# motorBoard.net
KiCad netlist of a schematic drawn in EAGLE
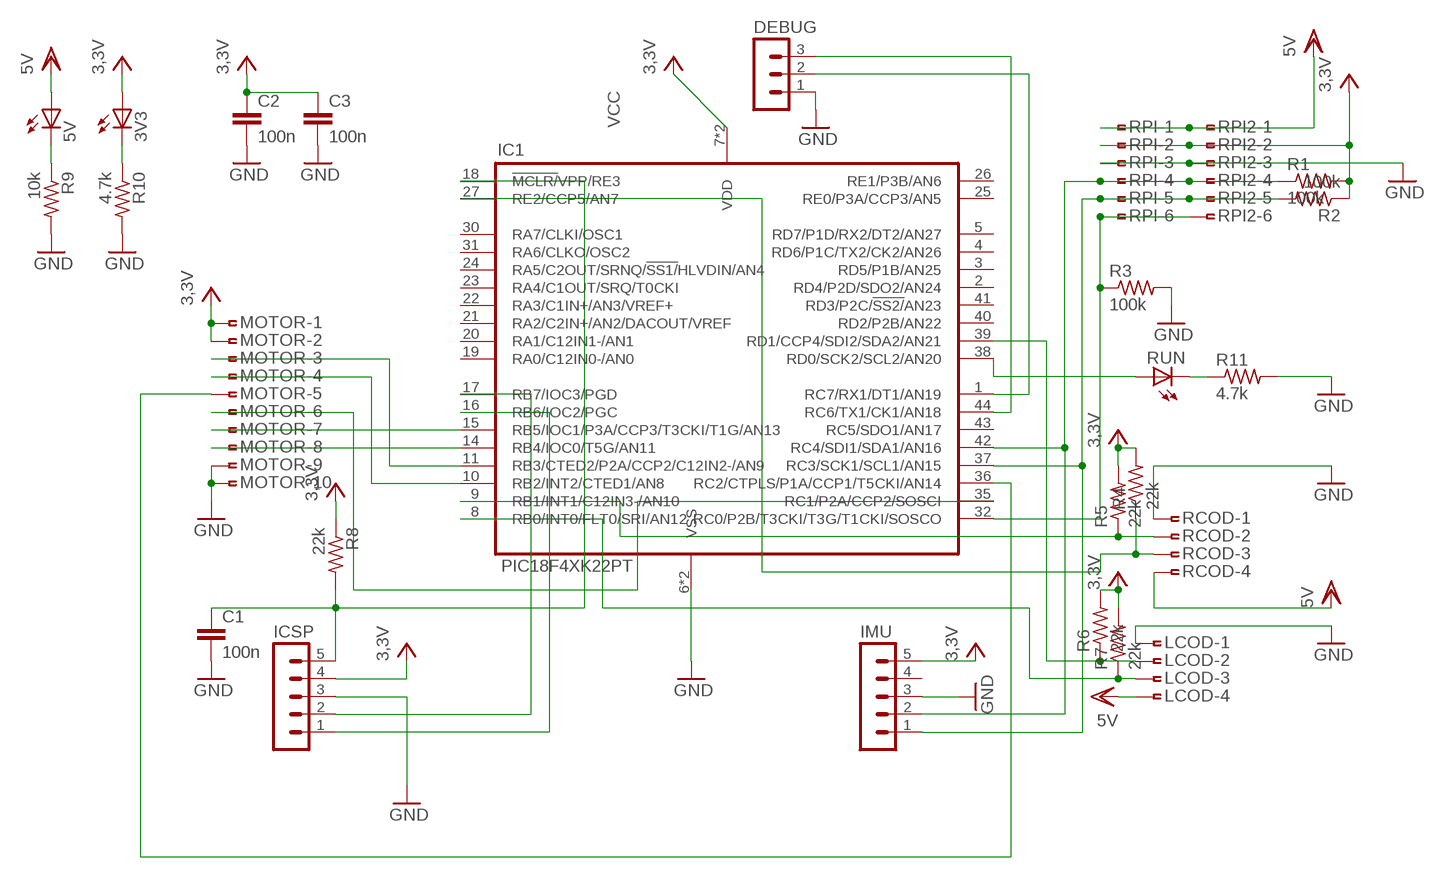
[diagram p0: schematic, sheet 1]

(export (version "E")
  (design (tool "Eeschema 10.0.6"))
  (components
    (comp (ref "3V3")
      (value "LEDCHIPLED_0805")
      (footprint "eagle-import:CHIPLED_0805")
      (libsource (lib "eagle-import") (part "LEDCHIPLED_0805"))
    )
    (comp (ref "5V")
      (value "LEDCHIPLED_0805")
      (footprint "eagle-import:CHIPLED_0805")
      (libsource (lib "eagle-import") (part "LEDCHIPLED_0805"))
    )
    (comp (ref "C1")
      (value "100n")
      (footprint "eagle-import:C0805")
      (libsource (lib "eagle-import") (part "C-EUC0805"))
    )
    (comp (ref "C2")
      (value "100n")
      (footprint "eagle-import:C0805")
      (libsource (lib "eagle-import") (part "C-EUC0805"))
    )
    (comp (ref "C3")
      (value "100n")
      (footprint "eagle-import:C0805")
      (libsource (lib "eagle-import") (part "C-EUC0805"))
    )
    (comp (ref "DEBUG")
      (value "MA03-1")
      (footprint "eagle-import:MA03-1")
      (libsource (lib "eagle-import") (part "MA03-1"))
    )
    (comp (ref "IC1")
      (value "PIC18F4XK22PT")
      (footprint "eagle-import:TQFP44")
      (libsource (lib "eagle-import") (part "PIC18F4XK22PT"))
    )
    (comp (ref "ICSP")
      (value "MA05-1")
      (footprint "eagle-import:MA05-1")
      (libsource (lib "eagle-import") (part "MA05-1"))
    )
    (comp (ref "IMU")
      (value "MA05-1")
      (footprint "eagle-import:MA05-1")
      (libsource (lib "eagle-import") (part "MA05-1"))
    )
    (comp (ref "LCOD")
      (value "SMDTOP-4")
      (footprint "eagle-import:SMDTOP4")
      (libsource (lib "eagle-import") (part "SMDTOP-4"))
    )
    (comp (ref "MOTOR")
      (value "SMDTOP-10")
      (footprint "eagle-import:SMDTOP10")
      (libsource (lib "eagle-import") (part "SMDTOP-10"))
    )
    (comp (ref "R1")
      (value "100k")
      (footprint "eagle-import:R0805")
      (libsource (lib "eagle-import") (part "R-US_R0805"))
    )
    (comp (ref "R2")
      (value "100k")
      (footprint "eagle-import:R0805")
      (libsource (lib "eagle-import") (part "R-US_R0805"))
    )
    (comp (ref "R3")
      (value "100k")
      (footprint "eagle-import:R0805")
      (libsource (lib "eagle-import") (part "R-US_R0805"))
    )
    (comp (ref "R4")
      (value "22k")
      (footprint "eagle-import:R0805")
      (libsource (lib "eagle-import") (part "R-US_R0805"))
    )
    (comp (ref "R5")
      (value "22k")
      (footprint "eagle-import:R0805")
      (libsource (lib "eagle-import") (part "R-US_R0805"))
    )
    (comp (ref "R6")
      (value "22k")
      (footprint "eagle-import:R0805")
      (libsource (lib "eagle-import") (part "R-US_R0805"))
    )
    (comp (ref "R7")
      (value "22k")
      (footprint "eagle-import:R0805")
      (libsource (lib "eagle-import") (part "R-US_R0805"))
    )
    (comp (ref "R8")
      (value "22k")
      (footprint "eagle-import:M0805")
      (libsource (lib "eagle-import") (part "R-US_M0805"))
    )
    (comp (ref "R9")
      (value "10k")
      (footprint "eagle-import:M0805")
      (libsource (lib "eagle-import") (part "R-US_M0805"))
    )
    (comp (ref "R10")
      (value "4.7k")
      (footprint "eagle-import:M0805")
      (libsource (lib "eagle-import") (part "R-US_M0805"))
    )
    (comp (ref "R11")
      (value "4.7k")
      (footprint "eagle-import:M0805")
      (libsource (lib "eagle-import") (part "R-US_M0805"))
    )
    (comp (ref "RCOD")
      (value "SMDTOP-4")
      (footprint "eagle-import:SMDTOP4")
      (libsource (lib "eagle-import") (part "SMDTOP-4"))
    )
    (comp (ref "RPI")
      (value "SMDTOP-6")
      (footprint "eagle-import:SMDTOP6")
      (libsource (lib "eagle-import") (part "SMDTOP-6"))
    )
    (comp (ref "RPI2")
      (value "SMDTOP-6")
      (footprint "eagle-import:SMDTOP6")
      (libsource (lib "eagle-import") (part "SMDTOP-6"))
    )
    (comp (ref "RUN")
      (value "LEDCHIPLED_0805")
      (footprint "eagle-import:CHIPLED_0805")
      (libsource (lib "eagle-import") (part "LEDCHIPLED_0805"))
    )
  )
  (nets
    (net (code "1") (name "3,3V") (class "Default")
      (node (ref "3V3") (pin "A") (pinfunction "A_A") (pintype "passive"))
      (node (ref "C2") (pin "1") (pinfunction "1_1") (pintype "passive"))
      (node (ref "C3") (pin "1") (pinfunction "1_1") (pintype "passive"))
      (node (ref "IC1") (pin "28") (pinfunction "VDD_28") (pintype "power_in"))
      (node (ref "IC1") (pin "7") (pinfunction "VDD_7") (pintype "power_in"))
      (node (ref "ICSP") (pin "4") (pinfunction "4_4") (pintype "passive"))
      (node (ref "IMU") (pin "5") (pinfunction "5_5") (pintype "passive"))
      (node (ref "MOTOR") (pin "1") (pinfunction "1_1") (pintype "passive"))
      (node (ref "MOTOR") (pin "2") (pinfunction "1_2") (pintype "passive"))
      (node (ref "R1") (pin "2") (pinfunction "2_2") (pintype "passive"))
      (node (ref "R2") (pin "1") (pinfunction "1_1") (pintype "passive"))
      (node (ref "R4") (pin "2") (pinfunction "2_2") (pintype "passive"))
      (node (ref "R5") (pin "2") (pinfunction "2_2") (pintype "passive"))
      (node (ref "R6") (pin "2") (pinfunction "2_2") (pintype "passive"))
      (node (ref "R7") (pin "2") (pinfunction "2_2") (pintype "passive"))
      (node (ref "R8") (pin "1") (pinfunction "1_1") (pintype "passive"))
      (node (ref "RPI") (pin "2") (pinfunction "1_2") (pintype "passive"))
      (node (ref "RPI2") (pin "2") (pinfunction "1_2") (pintype "passive"))
    )
    (net (code "2") (name "5V") (class "Default")
      (node (ref "5V") (pin "A") (pinfunction "A_A") (pintype "passive"))
      (node (ref "LCOD") (pin "4") (pinfunction "1_4") (pintype "passive"))
      (node (ref "RCOD") (pin "4") (pinfunction "1_4") (pintype "passive"))
      (node (ref "RPI") (pin "1") (pinfunction "1_1") (pintype "passive"))
      (node (ref "RPI2") (pin "1") (pinfunction "1_1") (pintype "passive"))
    )
    (net (code "3") (name "GND") (class "Default")
      (node (ref "C1") (pin "2") (pinfunction "2_2") (pintype "passive"))
      (node (ref "C2") (pin "2") (pinfunction "2_2") (pintype "passive"))
      (node (ref "C3") (pin "2") (pinfunction "2_2") (pintype "passive"))
      (node (ref "DEBUG") (pin "1") (pinfunction "1_1") (pintype "passive"))
      (node (ref "IC1") (pin "29") (pinfunction "VSS_29") (pintype "power_in"))
      (node (ref "IC1") (pin "6") (pinfunction "VSS_6") (pintype "power_in"))
      (node (ref "ICSP") (pin "3") (pinfunction "3_3") (pintype "passive"))
      (node (ref "IMU") (pin "3") (pinfunction "3_3") (pintype "passive"))
      (node (ref "LCOD") (pin "1") (pinfunction "1_1") (pintype "passive"))
      (node (ref "MOTOR") (pin "10") (pinfunction "1_10") (pintype "passive"))
      (node (ref "MOTOR") (pin "9") (pinfunction "1_9") (pintype "passive"))
      (node (ref "R10") (pin "2") (pinfunction "2_2") (pintype "passive"))
      (node (ref "R11") (pin "2") (pinfunction "2_2") (pintype "passive"))
      (node (ref "R3") (pin "2") (pinfunction "2_2") (pintype "passive"))
      (node (ref "R9") (pin "2") (pinfunction "2_2") (pintype "passive"))
      (node (ref "RCOD") (pin "1") (pinfunction "1_1") (pintype "passive"))
      (node (ref "RPI") (pin "3") (pinfunction "1_3") (pintype "passive"))
      (node (ref "RPI2") (pin "3") (pinfunction "1_3") (pintype "passive"))
    )
    (net (code "4") (name "Net-(3V3-PadC)") (class "Default")
      (node (ref "3V3") (pin "C") (pinfunction "C_C") (pintype "passive"))
      (node (ref "R10") (pin "1") (pinfunction "1_1") (pintype "passive"))
    )
    (net (code "5") (name "Net-(5V-PadC)") (class "Default")
      (node (ref "5V") (pin "C") (pinfunction "C_C") (pintype "passive"))
      (node (ref "R9") (pin "1") (pinfunction "1_1") (pintype "passive"))
    )
    (net (code "6") (name "Net-(IC1-RB0{slash}INT0{slash}FLT0{slash}SRI{slash}AN12)") (class "Default")
      (node (ref "IC1") (pin "8") (pinfunction "RB0/INT0/FLT0/SRI/AN12_8") (pintype "bidirectional"))
      (node (ref "LCOD") (pin "3") (pinfunction "1_3") (pintype "passive"))
      (node (ref "R7") (pin "1") (pinfunction "1_1") (pintype "passive"))
    )
    (net (code "7") (name "Net-(IC1-RB1{slash}INT1{slash}C12IN3-{slash}AN10)") (class "Default")
      (node (ref "IC1") (pin "9") (pinfunction "RB1/INT1/C12IN3-/AN10_9") (pintype "bidirectional"))
      (node (ref "R5") (pin "1") (pinfunction "1_1") (pintype "passive"))
      (node (ref "RCOD") (pin "2") (pinfunction "1_2") (pintype "passive"))
    )
    (net (code "8") (name "Net-(IC1-RB2{slash}INT2{slash}CTED1{slash}AN8)") (class "Default")
      (node (ref "IC1") (pin "10") (pinfunction "RB2/INT2/CTED1/AN8_10") (pintype "bidirectional"))
      (node (ref "MOTOR") (pin "4") (pinfunction "1_4") (pintype "passive"))
    )
    (net (code "9") (name "Net-(IC1-RB3{slash}CTED2{slash}P2A{slash}CCP2{slash}C12IN2-{slash}AN9)") (class "Default")
      (node (ref "IC1") (pin "11") (pinfunction "RB3/CTED2/P2A/CCP2/C12IN2-/AN9_11") (pintype "bidirectional"))
      (node (ref "MOTOR") (pin "3") (pinfunction "1_3") (pintype "passive"))
    )
    (net (code "10") (name "Net-(IC1-RB4{slash}IOC0{slash}T5G{slash}AN11)") (class "Default")
      (node (ref "IC1") (pin "14") (pinfunction "RB4/IOC0/T5G/AN11_14") (pintype "bidirectional"))
      (node (ref "MOTOR") (pin "8") (pinfunction "1_8") (pintype "passive"))
    )
    (net (code "11") (name "Net-(IC1-RB5{slash}IOC1{slash}P3A{slash}CCP3{slash}T3CKI{slash}T1G{slash}AN13)") (class "Default")
      (node (ref "IC1") (pin "15") (pinfunction "RB5/IOC1/P3A/CCP3/T3CKI/T1G/AN13_15") (pintype "bidirectional"))
      (node (ref "MOTOR") (pin "7") (pinfunction "1_7") (pintype "passive"))
    )
    (net (code "12") (name "Net-(IC1-RB6{slash}IOC2{slash}PGC)") (class "Default")
      (node (ref "IC1") (pin "16") (pinfunction "RB6/IOC2/PGC_16") (pintype "bidirectional"))
      (node (ref "ICSP") (pin "1") (pinfunction "1_1") (pintype "passive"))
    )
    (net (code "13") (name "Net-(IC1-RB7{slash}IOC3{slash}PGD)") (class "Default")
      (node (ref "IC1") (pin "17") (pinfunction "RB7/IOC3/PGD_17") (pintype "bidirectional"))
      (node (ref "ICSP") (pin "2") (pinfunction "2_2") (pintype "passive"))
    )
    (net (code "14") (name "Net-(IC1-RC0{slash}P2B{slash}T3CKI{slash}T3G{slash}T1CKI{slash}SOSCO)") (class "Default")
      (node (ref "IC1") (pin "32") (pinfunction "RC0/P2B/T3CKI/T3G/T1CKI/SOSCO_32") (pintype "bidirectional"))
      (node (ref "R3") (pin "1") (pinfunction "1_1") (pintype "passive"))
      (node (ref "RPI") (pin "6") (pinfunction "1_6") (pintype "passive"))
      (node (ref "RPI2") (pin "6") (pinfunction "1_6") (pintype "passive"))
    )
    (net (code "15") (name "Net-(IC1-RC1{slash}P2A{slash}CCP2{slash}SOSCI)") (class "Default")
      (node (ref "IC1") (pin "35") (pinfunction "RC1/P2A/CCP2/SOSCI_35") (pintype "bidirectional"))
      (node (ref "MOTOR") (pin "6") (pinfunction "1_6") (pintype "passive"))
    )
    (net (code "16") (name "Net-(IC1-RC2{slash}CTPLS{slash}P1A{slash}CCP1{slash}T5CKI{slash}AN14)") (class "Default")
      (node (ref "IC1") (pin "36") (pinfunction "RC2/CTPLS/P1A/CCP1/T5CKI/AN14_36") (pintype "bidirectional"))
      (node (ref "MOTOR") (pin "5") (pinfunction "1_5") (pintype "passive"))
    )
    (net (code "17") (name "Net-(IC1-RC3{slash}SCK1{slash}SCL1{slash}AN15)") (class "Default")
      (node (ref "IC1") (pin "37") (pinfunction "RC3/SCK1/SCL1/AN15_37") (pintype "bidirectional"))
      (node (ref "IMU") (pin "1") (pinfunction "1_1") (pintype "passive"))
      (node (ref "R2") (pin "2") (pinfunction "2_2") (pintype "passive"))
      (node (ref "RPI") (pin "5") (pinfunction "1_5") (pintype "passive"))
      (node (ref "RPI2") (pin "5") (pinfunction "1_5") (pintype "passive"))
    )
    (net (code "18") (name "Net-(IC1-RC4{slash}SDI1{slash}SDA1{slash}AN16)") (class "Default")
      (node (ref "IC1") (pin "42") (pinfunction "RC4/SDI1/SDA1/AN16_42") (pintype "bidirectional"))
      (node (ref "IMU") (pin "2") (pinfunction "2_2") (pintype "passive"))
      (node (ref "R1") (pin "1") (pinfunction "1_1") (pintype "passive"))
      (node (ref "RPI") (pin "4") (pinfunction "1_4") (pintype "passive"))
      (node (ref "RPI2") (pin "4") (pinfunction "1_4") (pintype "passive"))
    )
    (net (code "19") (name "Net-(IC1-RC6{slash}TX1{slash}CK1{slash}AN18)") (class "Default")
      (node (ref "DEBUG") (pin "3") (pinfunction "3_3") (pintype "passive"))
      (node (ref "IC1") (pin "44") (pinfunction "RC6/TX1/CK1/AN18_44") (pintype "bidirectional"))
    )
    (net (code "20") (name "Net-(IC1-RC7{slash}RX1{slash}DT1{slash}AN19)") (class "Default")
      (node (ref "DEBUG") (pin "2") (pinfunction "2_2") (pintype "passive"))
      (node (ref "IC1") (pin "1") (pinfunction "RC7/RX1/DT1/AN19_1") (pintype "bidirectional"))
    )
    (net (code "21") (name "Net-(IC1-RD0{slash}SCK2{slash}SCL2{slash}AN20)") (class "Default")
      (node (ref "IC1") (pin "38") (pinfunction "RD0/SCK2/SCL2/AN20_38") (pintype "bidirectional"))
      (node (ref "RUN") (pin "A") (pinfunction "A_A") (pintype "passive"))
    )
    (net (code "22") (name "Net-(IC1-RD1{slash}CCP4{slash}SDI2{slash}SDA2{slash}AN21)") (class "Default")
      (node (ref "IC1") (pin "39") (pinfunction "RD1/CCP4/SDI2/SDA2/AN21_39") (pintype "bidirectional"))
      (node (ref "LCOD") (pin "2") (pinfunction "1_2") (pintype "passive"))
      (node (ref "R6") (pin "1") (pinfunction "1_1") (pintype "passive"))
    )
    (net (code "23") (name "Net-(IC1-RE2{slash}CCP5{slash}AN7)") (class "Default")
      (node (ref "IC1") (pin "27") (pinfunction "RE2/CCP5/AN7_27") (pintype "bidirectional"))
      (node (ref "R4") (pin "1") (pinfunction "1_1") (pintype "passive"))
      (node (ref "RCOD") (pin "3") (pinfunction "1_3") (pintype "passive"))
    )
    (net (code "24") (name "Net-(IC1-~{MCLR{slash}}VPP{slash}RE3)") (class "Default")
      (node (ref "C1") (pin "1") (pinfunction "1_1") (pintype "passive"))
      (node (ref "IC1") (pin "18") (pinfunction "~{MCLR/}VPP/RE3_18") (pintype "input"))
      (node (ref "ICSP") (pin "5") (pinfunction "5_5") (pintype "passive"))
      (node (ref "R8") (pin "2") (pinfunction "2_2") (pintype "passive"))
    )
    (net (code "25") (name "Net-(R11-Pad1)") (class "Default")
      (node (ref "R11") (pin "1") (pinfunction "1_1") (pintype "passive"))
      (node (ref "RUN") (pin "C") (pinfunction "C_C") (pintype "passive"))
    )
    (net (code "26") (name "unconnected-(IC1-RA0{slash}C12IN0-{slash}AN0-Pad19)") (class "Default")
      (node (ref "IC1") (pin "19") (pinfunction "RA0/C12IN0-/AN0_19") (pintype "bidirectional"))
    )
    (net (code "27") (name "unconnected-(IC1-RA1{slash}C12IN1-{slash}AN1-Pad20)") (class "Default")
      (node (ref "IC1") (pin "20") (pinfunction "RA1/C12IN1-/AN1_20") (pintype "bidirectional"))
    )
    (net (code "28") (name "unconnected-(IC1-RA2{slash}C2IN+{slash}AN2{slash}DACOUT{slash}VREF-Pad21)") (class "Default")
      (node (ref "IC1") (pin "21") (pinfunction "RA2/C2IN+/AN2/DACOUT/VREF_21") (pintype "bidirectional"))
    )
    (net (code "29") (name "unconnected-(IC1-RA3{slash}C1IN+{slash}AN3{slash}VREF+-Pad22)") (class "Default")
      (node (ref "IC1") (pin "22") (pinfunction "RA3/C1IN+/AN3/VREF+_22") (pintype "bidirectional"))
    )
    (net (code "30") (name "unconnected-(IC1-RA4{slash}C1OUT{slash}SRQ{slash}T0CKI-Pad23)") (class "Default")
      (node (ref "IC1") (pin "23") (pinfunction "RA4/C1OUT/SRQ/T0CKI_23") (pintype "bidirectional"))
    )
    (net (code "31") (name "unconnected-(IC1-RA5{slash}C2OUT{slash}SRNQ{slash}~{SS1{slash}}HLVDIN{slash}AN4-Pad24)") (class "Default")
      (node (ref "IC1") (pin "24") (pinfunction "RA5/C2OUT/SRNQ/~{SS1/}HLVDIN/AN4_24") (pintype "bidirectional"))
    )
    (net (code "32") (name "unconnected-(IC1-RA6{slash}CLKO{slash}OSC2-Pad31)") (class "Default")
      (node (ref "IC1") (pin "31") (pinfunction "RA6/CLKO/OSC2_31") (pintype "bidirectional"))
    )
    (net (code "33") (name "unconnected-(IC1-RA7{slash}CLKI{slash}OSC1-Pad30)") (class "Default")
      (node (ref "IC1") (pin "30") (pinfunction "RA7/CLKI/OSC1_30") (pintype "bidirectional"))
    )
    (net (code "34") (name "unconnected-(IC1-RC5{slash}SDO1{slash}AN17-Pad43)") (class "Default")
      (node (ref "IC1") (pin "43") (pinfunction "RC5/SDO1/AN17_43") (pintype "bidirectional"))
    )
    (net (code "35") (name "unconnected-(IC1-RD2{slash}P2B{slash}AN22-Pad40)") (class "Default")
      (node (ref "IC1") (pin "40") (pinfunction "RD2/P2B/AN22_40") (pintype "bidirectional"))
    )
    (net (code "36") (name "unconnected-(IC1-RD3{slash}P2C{slash}~{SS2{slash}}AN23-Pad41)") (class "Default")
      (node (ref "IC1") (pin "41") (pinfunction "RD3/P2C/~{SS2/}AN23_41") (pintype "bidirectional"))
    )
    (net (code "37") (name "unconnected-(IC1-RD4{slash}P2D{slash}SDO2{slash}AN24-Pad2)") (class "Default")
      (node (ref "IC1") (pin "2") (pinfunction "RD4/P2D/SDO2/AN24_2") (pintype "bidirectional"))
    )
    (net (code "38") (name "unconnected-(IC1-RD5{slash}P1B{slash}AN25-Pad3)") (class "Default")
      (node (ref "IC1") (pin "3") (pinfunction "RD5/P1B/AN25_3") (pintype "bidirectional"))
    )
    (net (code "39") (name "unconnected-(IC1-RD6{slash}P1C{slash}TX2{slash}CK2{slash}AN26-Pad4)") (class "Default")
      (node (ref "IC1") (pin "4") (pinfunction "RD6/P1C/TX2/CK2/AN26_4") (pintype "bidirectional"))
    )
    (net (code "40") (name "unconnected-(IC1-RD7{slash}P1D{slash}RX2{slash}DT2{slash}AN27-Pad5)") (class "Default")
      (node (ref "IC1") (pin "5") (pinfunction "RD7/P1D/RX2/DT2/AN27_5") (pintype "bidirectional"))
    )
    (net (code "41") (name "unconnected-(IC1-RE0{slash}P3A{slash}CCP3{slash}AN5-Pad25)") (class "Default")
      (node (ref "IC1") (pin "25") (pinfunction "RE0/P3A/CCP3/AN5_25") (pintype "bidirectional"))
    )
    (net (code "42") (name "unconnected-(IC1-RE1{slash}P3B{slash}AN6-Pad26)") (class "Default")
      (node (ref "IC1") (pin "26") (pinfunction "RE1/P3B/AN6_26") (pintype "bidirectional"))
    )
    (net (code "43") (name "unconnected-(IMU-Pad4)") (class "Default")
      (node (ref "IMU") (pin "4") (pinfunction "4_4") (pintype "passive"))
    )
  )
)
